# Power.net
KiCad netlist of a schematic drawn in Altium Designer
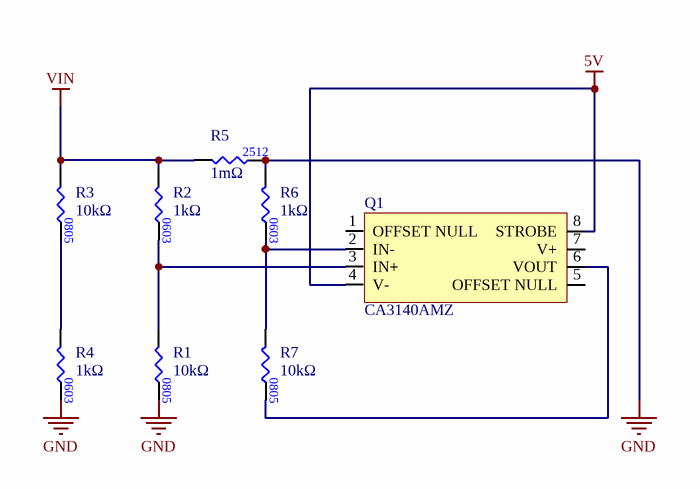
[diagram p0: Power.SchDoc]

(export (version "E")
  (design (tool "Eeschema 10.0.6"))
  (components
    (comp (ref "Q1")
      (value "OPAMP_CA3140AMZ")
      (footprint "CA3140AMZ")
      (description "IC OPAMP GP 1 CIRCUIT 8SOIC")
      (fields (field (name "MANUFACTURER PART NUMBER 1") "CA3140AMZ"))
      (libsource (lib "UWRT_Schematic_Library_2020") (part "OPAMP_CA3140AMZ"))
    )
    (comp (ref "R1")
      (value "10kΩ")
      (footprint "RES0805")
      (description "RES 10K OHM 5% 1/8W 0805")
      (fields (field (name "LCSC PART #") "C17414") (field (name "Comment") "RES_10kΩ_0805_5%"))
      (libsource (lib "UWRT_Schematic_Library_2020") (part "RES_10kΩ_0805_5%"))
    )
    (comp (ref "R2")
      (value "1kΩ")
      (footprint "RES0603")
      (description "RES 1K OHM 5% 1/10W 0603")
      (fields (field (name "Comment") "RES_1kΩ_0603_5%"))
      (libsource (lib "UWRT_Schematic_Library_2020") (part "RES_1kΩ_0603_5%"))
    )
    (comp (ref "R3")
      (value "10kΩ")
      (footprint "RES0805")
      (description "RES 10K OHM 5% 1/8W 0805")
      (fields (field (name "LCSC PART #") "C17414") (field (name "Comment") "RES_10kΩ_0805_5%"))
      (libsource (lib "UWRT_Schematic_Library_2020") (part "RES_10kΩ_0805_5%"))
    )
    (comp (ref "R4")
      (value "1kΩ")
      (footprint "RES0603")
      (description "RES 1K OHM 5% 1/10W 0603")
      (fields (field (name "Comment") "RES_1kΩ_0603_5%"))
      (libsource (lib "UWRT_Schematic_Library_2020") (part "RES_1kΩ_0603_5%"))
    )
    (comp (ref "R5")
      (value "1mΩ")
      (footprint "RESC6532X75N")
      (description "RES 1 mOHM 1% 3W 2512")
      (fields (field (name "Comment") "RES_1mΩ_2512_1%"))
      (libsource (lib "UWRT_Schematic_Library_2020") (part "RES_1mΩ_2512_1%"))
    )
    (comp (ref "R6")
      (value "1kΩ")
      (footprint "RES0603")
      (description "RES 1K OHM 5% 1/10W 0603")
      (fields (field (name "Comment") "RES_1kΩ_0603_5%"))
      (libsource (lib "UWRT_Schematic_Library_2020") (part "RES_1kΩ_0603_5%"))
    )
    (comp (ref "R7")
      (value "10kΩ")
      (footprint "RES0805")
      (description "RES 10K OHM 5% 1/8W 0805")
      (fields (field (name "LCSC PART #") "C17414") (field (name "Comment") "RES_10kΩ_0805_5%"))
      (libsource (lib "UWRT_Schematic_Library_2020") (part "RES_10kΩ_0805_5%"))
    )
  )
  (nets
    (net (code "1") (name "5V") (class "Default")
      (node (ref "Q1") (pin "4") (pinfunction "V-_4") (pintype "passive"))
      (node (ref "Q1") (pin "8") (pinfunction "STROBE_8") (pintype "passive"))
    )
    (net (code "2") (name "GND") (class "Default")
      (node (ref "R1") (pin "2") (pinfunction "2_2") (pintype "passive"))
      (node (ref "R4") (pin "2") (pinfunction "2_2") (pintype "passive"))
      (node (ref "R5") (pin "2") (pinfunction "2_2") (pintype "passive"))
      (node (ref "R6") (pin "1") (pinfunction "1_1") (pintype "passive"))
    )
    (net (code "3") (name "Net-(Q1-IN+)") (class "Default")
      (node (ref "Q1") (pin "3") (pinfunction "IN+_3") (pintype "passive"))
      (node (ref "R1") (pin "1") (pinfunction "1_1") (pintype "passive"))
      (node (ref "R2") (pin "2") (pinfunction "2_2") (pintype "passive"))
    )
    (net (code "4") (name "Net-(Q1-IN-)") (class "Default")
      (node (ref "Q1") (pin "2") (pinfunction "IN-_2") (pintype "passive"))
      (node (ref "R6") (pin "2") (pinfunction "2_2") (pintype "passive"))
      (node (ref "R7") (pin "1") (pinfunction "1_1") (pintype "passive"))
    )
    (net (code "5") (name "Net-(Q1-VOUT)") (class "Default")
      (node (ref "Q1") (pin "6") (pinfunction "VOUT_6") (pintype "passive"))
      (node (ref "R7") (pin "2") (pinfunction "2_2") (pintype "passive"))
    )
    (net (code "6") (name "Net-(R3-Pad2)") (class "Default")
      (node (ref "R3") (pin "2") (pinfunction "2_2") (pintype "passive"))
      (node (ref "R4") (pin "1") (pinfunction "1_1") (pintype "passive"))
    )
    (net (code "7") (name "VIN") (class "Default")
      (node (ref "R2") (pin "1") (pinfunction "1_1") (pintype "passive"))
      (node (ref "R3") (pin "1") (pinfunction "1_1") (pintype "passive"))
      (node (ref "R5") (pin "1") (pinfunction "1_1") (pintype "passive"))
    )
    (net (code "8") (name "unconnected-(Q1-OFFSET_NULL-Pad1)") (class "Default")
      (node (ref "Q1") (pin "1") (pinfunction "OFFSET_NULL_1") (pintype "passive"))
    )
    (net (code "9") (name "unconnected-(Q1-OFFSET_NULL-Pad5)") (class "Default")
      (node (ref "Q1") (pin "5") (pinfunction "OFFSET_NULL_5") (pintype "passive"))
    )
    (net (code "10") (name "unconnected-(Q1-V+-Pad7)") (class "Default")
      (node (ref "Q1") (pin "7") (pinfunction "V+_7") (pintype "passive"))
    )
  )
)
